# board.net
KiCad netlist of a schematic drawn in EAGLE
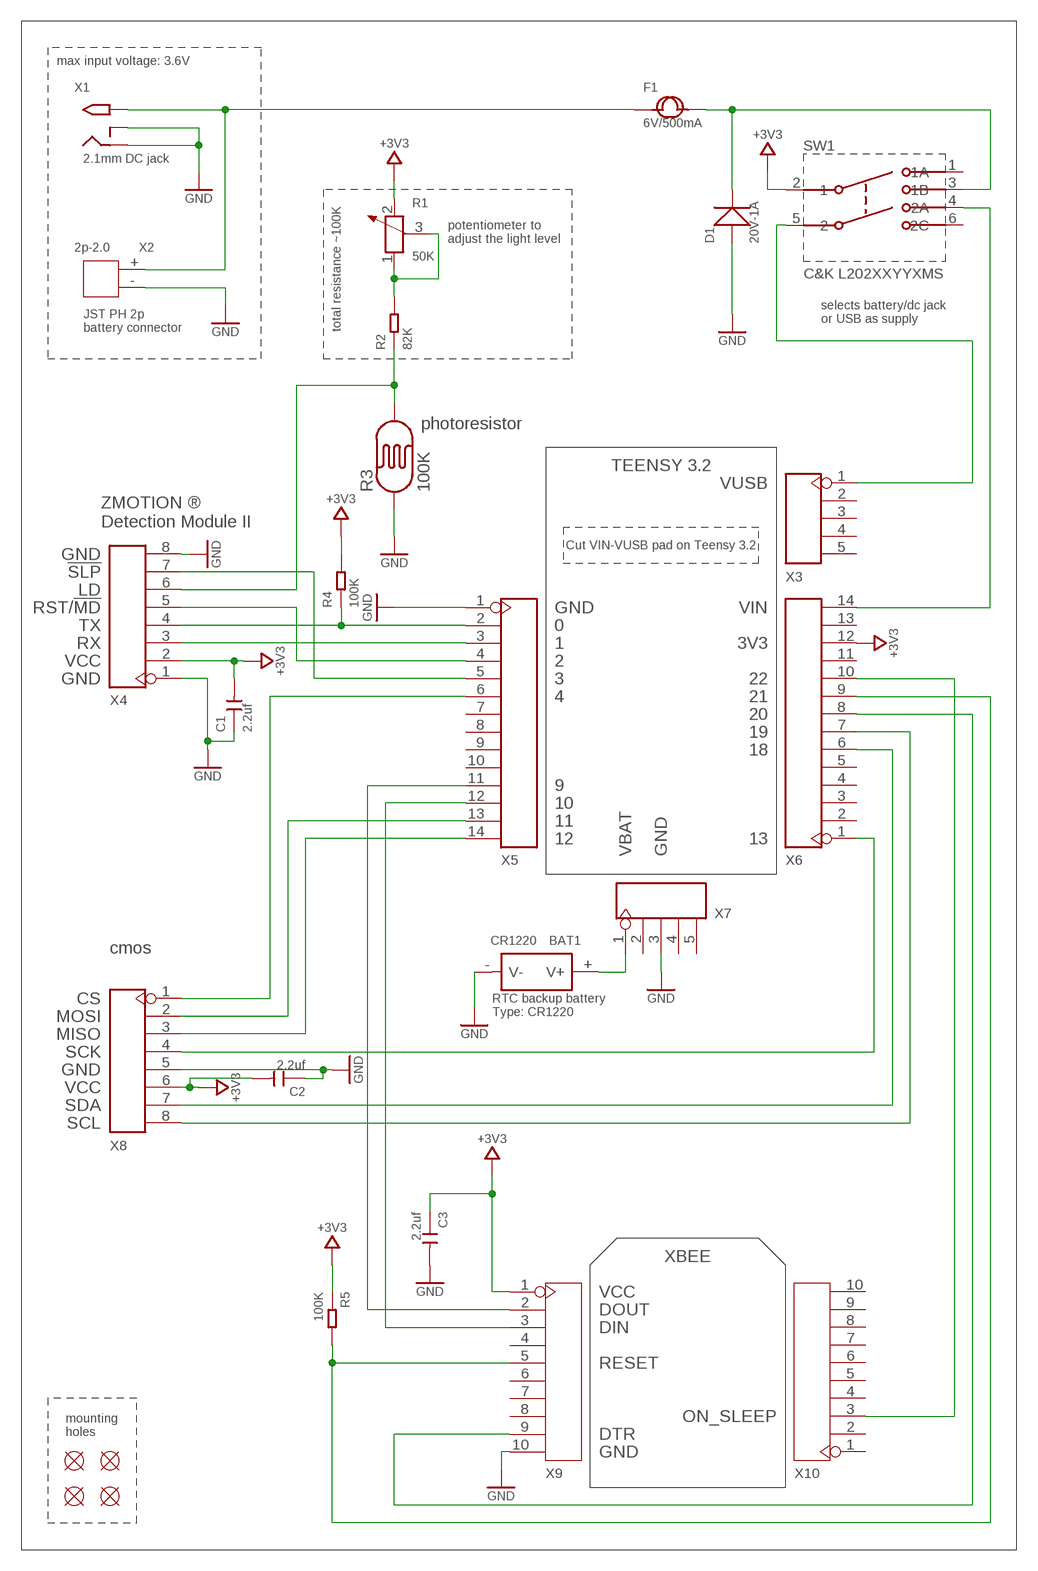
[diagram p0: schematic, sheet 1]

(export (version "E")
  (design (tool "Eeschema 10.0.6"))
  (components
    (comp (ref "BAT1")
      (value "CR1220")
      (footprint "eagle-import:BAT2P-SMD-16.4-CR1220")
      (libsource (lib "eagle-import") (part "SMD-BATTERY-CELL-HOLDER-PLASTIC"))
    )
    (comp (ref "C1")
      (value "2.2uf")
      (footprint "eagle-import:C0805")
      (fields (field (name "MPN") "CC0805KKX7R8BB225"))
      (libsource (lib "eagle-import") (part "CERAMIC-2.2UF-25V-10%-X7R(0805)"))
    )
    (comp (ref "C2")
      (value "2.2uf")
      (footprint "eagle-import:C0805")
      (fields (field (name "MPN") "CC0805KKX7R8BB225"))
      (libsource (lib "eagle-import") (part "CERAMIC-2.2UF-25V-10%-X7R(0805)"))
    )
    (comp (ref "C3")
      (value "2.2uf")
      (footprint "eagle-import:C0805")
      (fields (field (name "MPN") "CC0805KKX7R8BB225"))
      (libsource (lib "eagle-import") (part "CERAMIC-2.2UF-25V-10%-X7R(0805)"))
    )
    (comp (ref "D1")
      (value "20V-1A")
      (footprint "eagle-import:SOD-123")
      (fields (field (name "MPN") "B5819W"))
      (libsource (lib "eagle-import") (part "SMD-DIODE-SCHOTTKY-20V-1A(SOD-123)"))
    )
    (comp (ref "F1")
      (value "6V/500mA")
      (footprint "eagle-import:F1206")
      (fields (field (name "MPN") "SMD1206R500SF"))
      (libsource (lib "eagle-import") (part "SMD-PPTC-500MA(1206)"))
    )
    (comp (ref "MNT1")
      (value "MOUNTING_HOLE3.2MM_SILK")
      (footprint "eagle-import:HOLE_3.2MM_SILK")
      (libsource (lib "eagle-import") (part "MOUNTING_HOLE3.2MM_SILK"))
    )
    (comp (ref "MNT2")
      (value "MOUNTING_HOLE3.2MM_SILK")
      (footprint "eagle-import:HOLE_3.2MM_SILK")
      (libsource (lib "eagle-import") (part "MOUNTING_HOLE3.2MM_SILK"))
    )
    (comp (ref "MNT3")
      (value "MOUNTING_HOLE3.2MM_SILK")
      (footprint "eagle-import:HOLE_3.2MM_SILK")
      (libsource (lib "eagle-import") (part "MOUNTING_HOLE3.2MM_SILK"))
    )
    (comp (ref "MNT4")
      (value "MOUNTING_HOLE3.2MM_SILK")
      (footprint "eagle-import:HOLE_3.2MM_SILK")
      (libsource (lib "eagle-import") (part "MOUNTING_HOLE3.2MM_SILK"))
    )
    (comp (ref "R1")
      (value "50K")
      (footprint "eagle-import:ADJR3-7.0X7.0X5.0MM")
      (libsource (lib "eagle-import") (part "RES-ADJ-SX3362P"))
    )
    (comp (ref "R2")
      (value "82K")
      (footprint "eagle-import:R0805")
      (fields (field (name "MPN") "RC0805JR-0756KL"))
      (libsource (lib "eagle-import") (part "SMD-RES-56K-5%-1/(0805)"))
    )
    (comp (ref "R3")
      (value "100K")
      (footprint "eagle-import:CDS_4.2X3.4MM_PITCH_2.54MM")
      (libsource (lib "eagle-import") (part "CDS_PHOTOCELL_PHOTORESISTOR4.2X3.4MM_PITCH_2.54MM"))
    )
    (comp (ref "R4")
      (value "100K")
      (footprint "eagle-import:R0805")
      (fields (field (name "MPN") "RC0805FR-07100KL"))
      (libsource (lib "eagle-import") (part "SMD-RES-100K-1%-1/8W(0805)"))
    )
    (comp (ref "R5")
      (value "100K")
      (footprint "eagle-import:R0805")
      (fields (field (name "MPN") "RC0805FR-07100KL"))
      (libsource (lib "eagle-import") (part "SMD-RES-100K-1%-1/8W(0805)"))
    )
    (comp (ref "SW1")
      (value "C&K L202XXYYXMS")
      (footprint "eagle-import:C&K_L102_MS")
      (libsource (lib "eagle-import") (part "DPDTL202XXYYXMS"))
    )
    (comp (ref "X1")
      (value "2.1MMJACKTHM")
      (footprint "eagle-import:PJ-102A")
      (libsource (lib "eagle-import") (part "2.1MMJACKTHM"))
    )
    (comp (ref "X2")
      (value "2p-2.0")
      (footprint "eagle-import:H2-2.0-6X4.5MM")
      (libsource (lib "eagle-import") (part "DIP-JST-2P-2.0"))
    )
    (comp (ref "X3")
      (value "5p-2.54")
      (footprint "eagle-import:H5-2.54")
      (fields (field (name "MPN") "F185-1105A0BSYA1"))
      (libsource (lib "eagle-import") (part "DIP-BLACK-FEMALE-HEADER-VERT(5P-2.54)"))
    )
    (comp (ref "X4")
      (value "8p-2.54")
      (footprint "eagle-import:H8-2.54")
      (fields (field (name "MPN") "F185-1108A1BSYC1"))
      (libsource (lib "eagle-import") (part "DIP-BLACK-FEMALE-HEADER-VERT(8P-2.54)"))
    )
    (comp (ref "X5")
      (value "14p-2.54")
      (footprint "eagle-import:H14-2.54")
      (fields (field (name "MPN") "P125-1114A0BS116AX"))
      (libsource (lib "eagle-import") (part "DIP-YELLOW-MALE-HEADER-VERT(14P-2.54)"))
    )
    (comp (ref "X6")
      (value "14p-2.54")
      (footprint "eagle-import:H14-2.54")
      (fields (field (name "MPN") "P125-1114A0BS116AX"))
      (libsource (lib "eagle-import") (part "DIP-YELLOW-MALE-HEADER-VERT(14P-2.54)"))
    )
    (comp (ref "X7")
      (value "5p-2.54")
      (footprint "eagle-import:H5-2.54")
      (fields (field (name "MPN") "F185-1105A0BSYA1"))
      (libsource (lib "eagle-import") (part "DIP-BLACK-FEMALE-HEADER-VERT(5P-2.54)"))
    )
    (comp (ref "X8")
      (value "8p-2.54")
      (footprint "eagle-import:H8-2.54")
      (fields (field (name "MPN") "F185-1108A1BSYC1"))
      (libsource (lib "eagle-import") (part "DIP-BLACK-FEMALE-HEADER-VERT(8P-2.54)"))
    )
    (comp (ref "X9")
      (value "10p-2.0")
      (footprint "eagle-import:H10-2.0")
      (fields (field (name "MPN") "F243-1110A1BSUA1"))
      (libsource (lib "eagle-import") (part "DIP-BLACK-FEMALE-HEADER-VERT(10P-2.0)"))
    )
    (comp (ref "X10")
      (value "10p-2.0")
      (footprint "eagle-import:H10-2.0")
      (fields (field (name "MPN") "F243-1110A1BSUA1"))
      (libsource (lib "eagle-import") (part "DIP-BLACK-FEMALE-HEADER-VERT(10P-2.0)"))
    )
  )
  (nets
    (net (code "1") (name "+3V3") (class "Default")
      (node (ref "C1") (pin "2") (pinfunction "2_2") (pintype "passive"))
      (node (ref "C2") (pin "2") (pinfunction "2_2") (pintype "passive"))
      (node (ref "C3") (pin "1") (pinfunction "1_1") (pintype "passive"))
      (node (ref "R1") (pin "2") (pinfunction "3_2") (pintype "passive"))
      (node (ref "R4") (pin "2") (pinfunction "2_2") (pintype "passive"))
      (node (ref "R5") (pin "1") (pinfunction "1_1") (pintype "passive"))
      (node (ref "SW1") (pin "2") (pinfunction "1_2") (pintype "bidirectional"))
      (node (ref "X4") (pin "2") (pinfunction "2_2") (pintype "bidirectional"))
      (node (ref "X6") (pin "12") (pinfunction "12_12") (pintype "bidirectional"))
      (node (ref "X8") (pin "6") (pinfunction "6_6") (pintype "bidirectional"))
      (node (ref "X9") (pin "1") (pinfunction "1_1") (pintype "bidirectional"))
    )
    (net (code "2") (name "GND") (class "Default")
      (node (ref "BAT1") (pin "-") (pinfunction "V-_-") (pintype "bidirectional"))
      (node (ref "C1") (pin "1") (pinfunction "1_1") (pintype "passive"))
      (node (ref "C2") (pin "1") (pinfunction "1_1") (pintype "passive"))
      (node (ref "C3") (pin "2") (pinfunction "2_2") (pintype "passive"))
      (node (ref "D1") (pin "+") (pinfunction "+_+") (pintype "passive"))
      (node (ref "R3") (pin "P$1") (pinfunction "P$1_P$1") (pintype "bidirectional"))
      (node (ref "X1") (pin "RING") (pinfunction "RING_RING") (pintype "bidirectional"))
      (node (ref "X1") (pin "RING_SW") (pinfunction "RING_SW_RING_SW") (pintype "bidirectional"))
      (node (ref "X2") (pin "-") (pinfunction "P$2_-") (pintype "bidirectional"))
      (node (ref "X4") (pin "1") (pinfunction "1_1") (pintype "bidirectional"))
      (node (ref "X4") (pin "8") (pinfunction "8_8") (pintype "bidirectional"))
      (node (ref "X5") (pin "1") (pinfunction "1_1") (pintype "bidirectional"))
      (node (ref "X7") (pin "3") (pinfunction "3_3") (pintype "bidirectional"))
      (node (ref "X8") (pin "5") (pinfunction "5_5") (pintype "bidirectional"))
      (node (ref "X9") (pin "10") (pinfunction "10_10") (pintype "bidirectional"))
    )
    (net (code "3") (name "Net-(BAT1-V+)") (class "Default")
      (node (ref "BAT1") (pin "+") (pinfunction "V+_+") (pintype "bidirectional"))
      (node (ref "X7") (pin "1") (pinfunction "1_1") (pintype "bidirectional"))
    )
    (net (code "4") (name "Net-(R1-2)") (class "Default")
      (node (ref "R1") (pin "1") (pinfunction "1_1") (pintype "passive"))
      (node (ref "R1") (pin "3") (pinfunction "2_3") (pintype "passive"))
      (node (ref "R2") (pin "2") (pinfunction "2_2") (pintype "passive"))
    )
    (net (code "5") (name "Net-(R2-Pad1)") (class "Default")
      (node (ref "R2") (pin "1") (pinfunction "1_1") (pintype "passive"))
      (node (ref "R3") (pin "P$2") (pinfunction "P$2_P$2") (pintype "bidirectional"))
      (node (ref "X4") (pin "6") (pinfunction "6_6") (pintype "bidirectional"))
    )
    (net (code "6") (name "Net-(R4-Pad1)") (class "Default")
      (node (ref "R4") (pin "1") (pinfunction "1_1") (pintype "passive"))
      (node (ref "X4") (pin "4") (pinfunction "4_4") (pintype "bidirectional"))
      (node (ref "X5") (pin "2") (pinfunction "2_2") (pintype "bidirectional"))
    )
    (net (code "7") (name "Net-(R5-Pad2)") (class "Default")
      (node (ref "R5") (pin "2") (pinfunction "2_2") (pintype "passive"))
      (node (ref "X6") (pin "9") (pinfunction "9_9") (pintype "bidirectional"))
      (node (ref "X9") (pin "5") (pinfunction "5_5") (pintype "bidirectional"))
    )
    (net (code "8") (name "Net-(SW1-1B)") (class "Default")
      (node (ref "D1") (pin "-") (pinfunction "-_-") (pintype "passive"))
      (node (ref "F1") (pin "2") (pinfunction "2_2") (pintype "bidirectional"))
      (node (ref "SW1") (pin "3") (pinfunction "1B_3") (pintype "bidirectional"))
    )
    (net (code "9") (name "Net-(SW1-2)") (class "Default")
      (node (ref "SW1") (pin "5") (pinfunction "2_5") (pintype "bidirectional"))
      (node (ref "X3") (pin "1") (pinfunction "1_1") (pintype "bidirectional"))
    )
    (net (code "10") (name "Net-(SW1-2A)") (class "Default")
      (node (ref "SW1") (pin "4") (pinfunction "2A_4") (pintype "bidirectional"))
      (node (ref "X6") (pin "14") (pinfunction "14_14") (pintype "bidirectional"))
    )
    (net (code "11") (name "Net-(X2-P$1)") (class "Default")
      (node (ref "F1") (pin "1") (pinfunction "1_1") (pintype "bidirectional"))
      (node (ref "X1") (pin "TIP") (pinfunction "TIP_TIP") (pintype "bidirectional"))
      (node (ref "X2") (pin "+") (pinfunction "P$1_+") (pintype "bidirectional"))
    )
    (net (code "12") (name "Net-(X4-Pad3)") (class "Default")
      (node (ref "X4") (pin "3") (pinfunction "3_3") (pintype "bidirectional"))
      (node (ref "X5") (pin "3") (pinfunction "3_3") (pintype "bidirectional"))
    )
    (net (code "13") (name "Net-(X4-Pad5)") (class "Default")
      (node (ref "X4") (pin "5") (pinfunction "5_5") (pintype "bidirectional"))
      (node (ref "X5") (pin "4") (pinfunction "4_4") (pintype "bidirectional"))
    )
    (net (code "14") (name "Net-(X4-Pad7)") (class "Default")
      (node (ref "X4") (pin "7") (pinfunction "7_7") (pintype "bidirectional"))
      (node (ref "X5") (pin "5") (pinfunction "5_5") (pintype "bidirectional"))
    )
    (net (code "15") (name "Net-(X5-Pad6)") (class "Default")
      (node (ref "X5") (pin "6") (pinfunction "6_6") (pintype "bidirectional"))
      (node (ref "X8") (pin "1") (pinfunction "1_1") (pintype "bidirectional"))
    )
    (net (code "16") (name "Net-(X5-Pad11)") (class "Default")
      (node (ref "X5") (pin "11") (pinfunction "11_11") (pintype "bidirectional"))
      (node (ref "X9") (pin "2") (pinfunction "2_2") (pintype "bidirectional"))
    )
    (net (code "17") (name "Net-(X5-Pad12)") (class "Default")
      (node (ref "X5") (pin "12") (pinfunction "12_12") (pintype "bidirectional"))
      (node (ref "X9") (pin "3") (pinfunction "3_3") (pintype "bidirectional"))
    )
    (net (code "18") (name "Net-(X5-Pad13)") (class "Default")
      (node (ref "X5") (pin "13") (pinfunction "13_13") (pintype "bidirectional"))
      (node (ref "X8") (pin "2") (pinfunction "2_2") (pintype "bidirectional"))
    )
    (net (code "19") (name "Net-(X5-Pad14)") (class "Default")
      (node (ref "X5") (pin "14") (pinfunction "14_14") (pintype "bidirectional"))
      (node (ref "X8") (pin "3") (pinfunction "3_3") (pintype "bidirectional"))
    )
    (net (code "20") (name "Net-(X6-Pad1)") (class "Default")
      (node (ref "X6") (pin "1") (pinfunction "1_1") (pintype "bidirectional"))
      (node (ref "X8") (pin "4") (pinfunction "4_4") (pintype "bidirectional"))
    )
    (net (code "21") (name "Net-(X6-Pad6)") (class "Default")
      (node (ref "X6") (pin "6") (pinfunction "6_6") (pintype "bidirectional"))
      (node (ref "X8") (pin "7") (pinfunction "7_7") (pintype "bidirectional"))
    )
    (net (code "22") (name "Net-(X6-Pad7)") (class "Default")
      (node (ref "X6") (pin "7") (pinfunction "7_7") (pintype "bidirectional"))
      (node (ref "X8") (pin "8") (pinfunction "8_8") (pintype "bidirectional"))
    )
    (net (code "23") (name "Net-(X6-Pad8)") (class "Default")
      (node (ref "X6") (pin "8") (pinfunction "8_8") (pintype "bidirectional"))
      (node (ref "X9") (pin "9") (pinfunction "9_9") (pintype "bidirectional"))
    )
    (net (code "24") (name "Net-(X10-Pad3)") (class "Default")
      (node (ref "X10") (pin "3") (pinfunction "3_3") (pintype "bidirectional"))
      (node (ref "X6") (pin "10") (pinfunction "10_10") (pintype "bidirectional"))
    )
    (net (code "25") (name "unconnected-(SW1-1A-Pad1)") (class "Default")
      (node (ref "SW1") (pin "1") (pinfunction "1A_1") (pintype "bidirectional"))
    )
    (net (code "26") (name "unconnected-(SW1-2C-Pad6)") (class "Default")
      (node (ref "SW1") (pin "6") (pinfunction "2C_6") (pintype "bidirectional"))
    )
    (net (code "27") (name "unconnected-(X3-Pad2)") (class "Default")
      (node (ref "X3") (pin "2") (pinfunction "2_2") (pintype "bidirectional"))
    )
    (net (code "28") (name "unconnected-(X3-Pad3)") (class "Default")
      (node (ref "X3") (pin "3") (pinfunction "3_3") (pintype "bidirectional"))
    )
    (net (code "29") (name "unconnected-(X3-Pad4)") (class "Default")
      (node (ref "X3") (pin "4") (pinfunction "4_4") (pintype "bidirectional"))
    )
    (net (code "30") (name "unconnected-(X3-Pad5)") (class "Default")
      (node (ref "X3") (pin "5") (pinfunction "5_5") (pintype "bidirectional"))
    )
    (net (code "31") (name "unconnected-(X5-Pad7)") (class "Default")
      (node (ref "X5") (pin "7") (pinfunction "7_7") (pintype "bidirectional"))
    )
    (net (code "32") (name "unconnected-(X5-Pad8)") (class "Default")
      (node (ref "X5") (pin "8") (pinfunction "8_8") (pintype "bidirectional"))
    )
    (net (code "33") (name "unconnected-(X5-Pad9)") (class "Default")
      (node (ref "X5") (pin "9") (pinfunction "9_9") (pintype "bidirectional"))
    )
    (net (code "34") (name "unconnected-(X5-Pad10)") (class "Default")
      (node (ref "X5") (pin "10") (pinfunction "10_10") (pintype "bidirectional"))
    )
    (net (code "35") (name "unconnected-(X6-Pad2)") (class "Default")
      (node (ref "X6") (pin "2") (pinfunction "2_2") (pintype "bidirectional"))
    )
    (net (code "36") (name "unconnected-(X6-Pad3)") (class "Default")
      (node (ref "X6") (pin "3") (pinfunction "3_3") (pintype "bidirectional"))
    )
    (net (code "37") (name "unconnected-(X6-Pad4)") (class "Default")
      (node (ref "X6") (pin "4") (pinfunction "4_4") (pintype "bidirectional"))
    )
    (net (code "38") (name "unconnected-(X6-Pad5)") (class "Default")
      (node (ref "X6") (pin "5") (pinfunction "5_5") (pintype "bidirectional"))
    )
    (net (code "39") (name "unconnected-(X6-Pad11)") (class "Default")
      (node (ref "X6") (pin "11") (pinfunction "11_11") (pintype "bidirectional"))
    )
    (net (code "40") (name "unconnected-(X6-Pad13)") (class "Default")
      (node (ref "X6") (pin "13") (pinfunction "13_13") (pintype "bidirectional"))
    )
    (net (code "41") (name "unconnected-(X7-Pad2)") (class "Default")
      (node (ref "X7") (pin "2") (pinfunction "2_2") (pintype "bidirectional"))
    )
    (net (code "42") (name "unconnected-(X7-Pad4)") (class "Default")
      (node (ref "X7") (pin "4") (pinfunction "4_4") (pintype "bidirectional"))
    )
    (net (code "43") (name "unconnected-(X7-Pad5)") (class "Default")
      (node (ref "X7") (pin "5") (pinfunction "5_5") (pintype "bidirectional"))
    )
    (net (code "44") (name "unconnected-(X9-Pad4)") (class "Default")
      (node (ref "X9") (pin "4") (pinfunction "4_4") (pintype "bidirectional"))
    )
    (net (code "45") (name "unconnected-(X9-Pad6)") (class "Default")
      (node (ref "X9") (pin "6") (pinfunction "6_6") (pintype "bidirectional"))
    )
    (net (code "46") (name "unconnected-(X9-Pad7)") (class "Default")
      (node (ref "X9") (pin "7") (pinfunction "7_7") (pintype "bidirectional"))
    )
    (net (code "47") (name "unconnected-(X9-Pad8)") (class "Default")
      (node (ref "X9") (pin "8") (pinfunction "8_8") (pintype "bidirectional"))
    )
    (net (code "48") (name "unconnected-(X10-Pad1)") (class "Default")
      (node (ref "X10") (pin "1") (pinfunction "1_1") (pintype "bidirectional"))
    )
    (net (code "49") (name "unconnected-(X10-Pad2)") (class "Default")
      (node (ref "X10") (pin "2") (pinfunction "2_2") (pintype "bidirectional"))
    )
    (net (code "50") (name "unconnected-(X10-Pad4)") (class "Default")
      (node (ref "X10") (pin "4") (pinfunction "4_4") (pintype "bidirectional"))
    )
    (net (code "51") (name "unconnected-(X10-Pad5)") (class "Default")
      (node (ref "X10") (pin "5") (pinfunction "5_5") (pintype "bidirectional"))
    )
    (net (code "52") (name "unconnected-(X10-Pad6)") (class "Default")
      (node (ref "X10") (pin "6") (pinfunction "6_6") (pintype "bidirectional"))
    )
    (net (code "53") (name "unconnected-(X10-Pad7)") (class "Default")
      (node (ref "X10") (pin "7") (pinfunction "7_7") (pintype "bidirectional"))
    )
    (net (code "54") (name "unconnected-(X10-Pad8)") (class "Default")
      (node (ref "X10") (pin "8") (pinfunction "8_8") (pintype "bidirectional"))
    )
    (net (code "55") (name "unconnected-(X10-Pad9)") (class "Default")
      (node (ref "X10") (pin "9") (pinfunction "9_9") (pintype "bidirectional"))
    )
    (net (code "56") (name "unconnected-(X10-Pad10)") (class "Default")
      (node (ref "X10") (pin "10") (pinfunction "10_10") (pintype "bidirectional"))
    )
  )
)
